# 3Dprinter-laser-master.net
KiCad netlist of a schematic drawn in EasyEDA
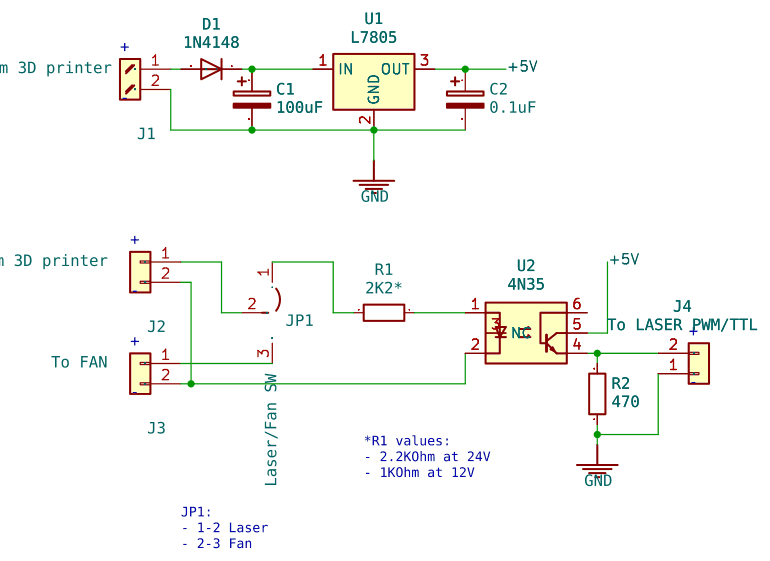
[diagram p0: schematic sheet]

(export (version "E")
  (design (tool "Eeschema 10.0.6"))
  (components
    (comp (ref "C1") (value "100uF") (libsource (lib "") (part "Unknown_220_105")))
    (comp (ref "C2") (value "0.1uF") (libsource (lib "") (part "Unknown_325_105")))
    (comp (ref "D1") (value "1N4148") (libsource (lib "") (part "Unknown_200_90")))
    (comp (ref "J1") (value "12/24V from 3D printer") (libsource (lib "") (part "Unknown_160_90")))
    (comp (ref "J2") (value "FAN from 3D printer") (libsource (lib "") (part "Unknown_165_185")))
    (comp (ref "J3") (value "To FAN") (libsource (lib "") (part "Unknown_165_235")))
    (comp (ref "J4") (value "To LASER PWM/TTL") (libsource (lib "") (part "Unknown_440_240")))
    (comp (ref "JP1") (value "Laser/Fan SW") (libsource (lib "") (part "Unknown_230_210")))
    (comp (ref "R1") (value "2K2*") (libsource (lib "") (part "Unknown_285_210")))
    (comp (ref "R2") (value "470") (libsource (lib "") (part "Unknown_390_250")))
    (comp (ref "U1") (value "L7805") (libsource (lib "") (part "Unknown_280_90")))
    (comp (ref "U2") (value "4N35") (libsource (lib "") (part "Unknown_355_220")))
  )
  (nets
    (net (code "1") (name "/+5V") (class "Default")
      (node (ref "C2") (pin "1") (pintype "unspecified"))
      (node (ref "U1") (pin "3") (pinfunction "OUT_3") (pintype "bidirectional"))
      (node (ref "U2") (pin "5") (pintype "unspecified"))
    )
    (net (code "2") (name "GND") (class "Default")
      (node (ref "C1") (pin "2") (pintype "unspecified"))
      (node (ref "C2") (pin "2") (pintype "unspecified"))
      (node (ref "J1") (pin "2") (pinfunction "Pin_2_2") (pintype "unspecified"))
      (node (ref "J4") (pin "1") (pinfunction "Pin_1_1") (pintype "unspecified"))
      (node (ref "R2") (pin "1") (pintype "unspecified"))
      (node (ref "U1") (pin "2") (pinfunction "GND_2") (pintype "bidirectional"))
    )
    (net (code "3") (name "Net-(D1-A)") (class "Default")
      (node (ref "D1") (pin "2") (pinfunction "A_2") (pintype "unspecified"))
      (node (ref "J1") (pin "1") (pinfunction "Pin_1_1") (pintype "unspecified"))
    )
    (net (code "4") (name "Net-(D1-K)") (class "Default")
      (node (ref "C1") (pin "1") (pintype "unspecified"))
      (node (ref "D1") (pin "1") (pinfunction "K_1") (pintype "unspecified"))
      (node (ref "U1") (pin "1") (pinfunction "IN_1") (pintype "bidirectional"))
    )
    (net (code "5") (name "Net-(J2-Pin_1)") (class "Default")
      (node (ref "J2") (pin "1") (pinfunction "Pin_1_1") (pintype "unspecified"))
      (node (ref "JP1") (pin "2") (pinfunction "C_2") (pintype "input"))
    )
    (net (code "6") (name "Net-(J2-Pin_2)") (class "Default")
      (node (ref "J2") (pin "2") (pinfunction "Pin_2_2") (pintype "unspecified"))
      (node (ref "J3") (pin "2") (pinfunction "Pin_2_2") (pintype "unspecified"))
      (node (ref "U2") (pin "2") (pintype "unspecified"))
    )
    (net (code "7") (name "Net-(J3-Pin_1)") (class "Default")
      (node (ref "J3") (pin "1") (pinfunction "Pin_1_1") (pintype "unspecified"))
      (node (ref "JP1") (pin "3") (pinfunction "B_3") (pintype "unspecified"))
    )
    (net (code "8") (name "Net-(J4-Pin_2)") (class "Default")
      (node (ref "J4") (pin "2") (pinfunction "Pin_2_2") (pintype "unspecified"))
      (node (ref "R2") (pin "2") (pintype "unspecified"))
      (node (ref "U2") (pin "4") (pintype "unspecified"))
    )
    (net (code "9") (name "Net-(JP1-A)") (class "Default")
      (node (ref "JP1") (pin "1") (pinfunction "A_1") (pintype "unspecified"))
      (node (ref "R1") (pin "2") (pintype "unspecified"))
    )
    (net (code "10") (name "Net-(R1-Pad1)") (class "Default")
      (node (ref "R1") (pin "1") (pintype "unspecified"))
      (node (ref "U2") (pin "1") (pintype "unspecified"))
    )
    (net (code "11") (name "unconnected-(U2-NC-Pad3)") (class "Default")
      (node (ref "U2") (pin "3") (pinfunction "NC_3") (pintype "bidirectional"))
    )
    (net (code "12") (name "unconnected-(U2-Pad6)") (class "Default")
      (node (ref "U2") (pin "6") (pintype "unspecified"))
    )
  )
)
